# SparkFun_Valve_Control_Shield.net
KiCad netlist of a schematic drawn in EAGLE
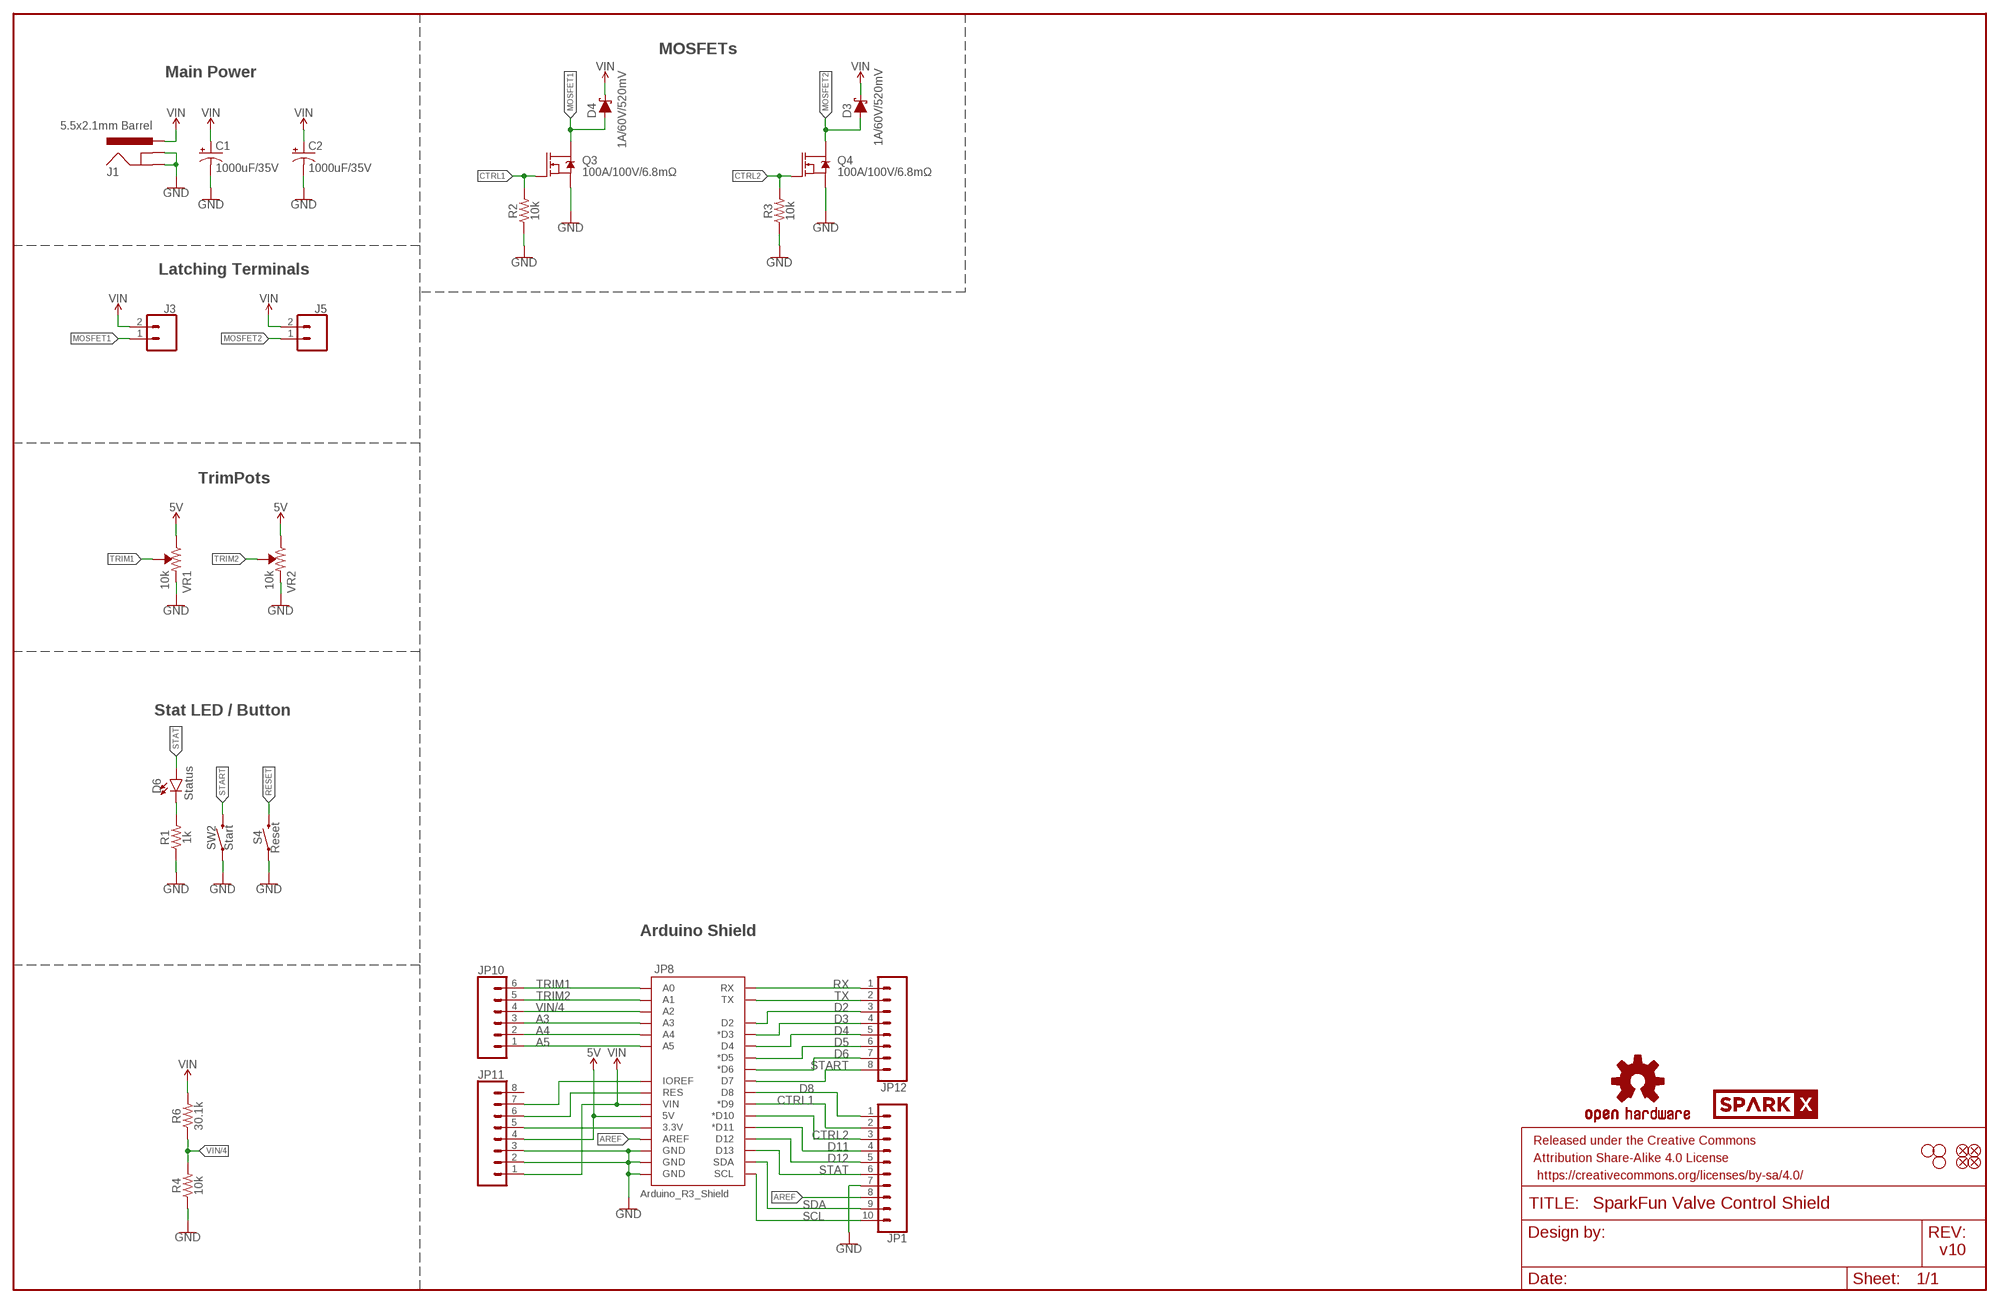
[diagram p0: schematic, sheet 1]

(export (version "E")
  (design (tool "Eeschema 10.0.6"))
  (components
    (comp (ref "C1")
      (value "1000uF/35V")
      (footprint "eagle-import:CPOL-RADIAL-5MM-10MM-KIT")
      (libsource (lib "eagle-import") (part "1000UF-RADIAL-5MM-35V-20%-KIT"))
    )
    (comp (ref "C2")
      (value "1000uF/35V")
      (footprint "eagle-import:CPOL-RADIAL-5MM-10MM-KIT")
      (libsource (lib "eagle-import") (part "1000UF-RADIAL-5MM-35V-20%-KIT"))
    )
    (comp (ref "D3")
      (value "1A/60V/520mV")
      (footprint "eagle-import:DIODE-MICRO-SMP")
      (libsource (lib "eagle-import") (part "DIODE-SCHOTTKY-MSS1P6-M3/89A"))
    )
    (comp (ref "D4")
      (value "1A/60V/520mV")
      (footprint "eagle-import:DIODE-MICRO-SMP")
      (libsource (lib "eagle-import") (part "DIODE-SCHOTTKY-MSS1P6-M3/89A"))
    )
    (comp (ref "D6")
      (value "Status")
      (footprint "eagle-import:LED-1206")
      (libsource (lib "eagle-import") (part "LED1206"))
    )
    (comp (ref "FD1")
      (value "FIDUCIAL1X2")
      (footprint "eagle-import:FIDUCIAL-1X2")
      (libsource (lib "eagle-import") (part "FIDUCIAL1X2"))
    )
    (comp (ref "FD2")
      (value "FIDUCIAL1X2")
      (footprint "eagle-import:FIDUCIAL-1X2")
      (libsource (lib "eagle-import") (part "FIDUCIAL1X2"))
    )
    (comp (ref "FD3")
      (value "FIDUCIAL1X2")
      (footprint "eagle-import:FIDUCIAL-1X2")
      (libsource (lib "eagle-import") (part "FIDUCIAL1X2"))
    )
    (comp (ref "FD4")
      (value "FIDUCIAL1X2")
      (footprint "eagle-import:FIDUCIAL-1X2")
      (libsource (lib "eagle-import") (part "FIDUCIAL1X2"))
    )
    (comp (ref "FRAME2")
      (value "FRAME-LEDGER")
      (footprint "eagle-import:CREATIVE_COMMONS")
      (libsource (lib "eagle-import") (part "FRAME-LEDGER"))
    )
    (comp (ref "H1")
      (value "STAND-OFF")
      (footprint "eagle-import:STAND-OFF")
      (libsource (lib "eagle-import") (part "STAND-OFF"))
    )
    (comp (ref "H2")
      (value "STAND-OFF")
      (footprint "eagle-import:STAND-OFF")
      (libsource (lib "eagle-import") (part "STAND-OFF"))
    )
    (comp (ref "H4")
      (value "STAND-OFF")
      (footprint "eagle-import:STAND-OFF")
      (libsource (lib "eagle-import") (part "STAND-OFF"))
    )
    (comp (ref "J1")
      (value "5.5x2.1mm Barrel")
      (footprint "eagle-import:POWER_JACK_SMD")
      (libsource (lib "eagle-import") (part "POWER_JACKSMD"))
    )
    (comp (ref "J3")
      (value "CONN_02LATCH_2")
      (footprint "eagle-import:LATCHTERMINAL-5MM-2")
      (libsource (lib "eagle-import") (part "CONN_02LATCH_2"))
    )
    (comp (ref "J5")
      (value "CONN_02LATCH_2")
      (footprint "eagle-import:LATCHTERMINAL-5MM-2")
      (libsource (lib "eagle-import") (part "CONN_02LATCH_2"))
    )
    (comp (ref "JP1")
      (value "CONN_10NO_SILK_PTH_FEMALE")
      (footprint "eagle-import:1X10_NO_SILK")
      (libsource (lib "eagle-import") (part "CONN_10NO_SILK_PTH_FEMALE"))
    )
    (comp (ref "JP8")
      (value "ARDUINO_R3_SHIELDNOLABELS")
      (footprint "eagle-import:UNO_R3_SHIELD_NOLABELS")
      (libsource (lib "eagle-import") (part "ARDUINO_R3_SHIELDNOLABELS"))
    )
    (comp (ref "JP10")
      (value "CONN_06NO_SILK_NO_POP")
      (footprint "eagle-import:1X06_NO_SILK")
      (libsource (lib "eagle-import") (part "CONN_06NO_SILK_NO_POP"))
    )
    (comp (ref "JP11")
      (value "CONN_08NO_SILK_FEMALE_PTH")
      (footprint "eagle-import:1X08_NO_SILK")
      (libsource (lib "eagle-import") (part "CONN_08NO_SILK_FEMALE_PTH"))
    )
    (comp (ref "JP12")
      (value "CONN_08NO_SILK_FEMALE_PTH")
      (footprint "eagle-import:1X08_NO_SILK")
      (libsource (lib "eagle-import") (part "CONN_08NO_SILK_FEMALE_PTH"))
    )
    (comp (ref "LOGO1")
      (value "OSHW-LOGOS")
      (footprint "eagle-import:OSHW-LOGO-S")
      (libsource (lib "eagle-import") (part "OSHW-LOGOS"))
    )
    (comp (ref "Q3")
      (value "100A/100V/6.8mΩ")
      (footprint "eagle-import:TO-263_D2PAK")
      (libsource (lib "eagle-import") (part "MOSFET-NCH-PSMN7R0"))
    )
    (comp (ref "Q4")
      (value "100A/100V/6.8mΩ")
      (footprint "eagle-import:TO-263_D2PAK")
      (libsource (lib "eagle-import") (part "MOSFET-NCH-PSMN7R0"))
    )
    (comp (ref "R1")
      (value "1k")
      (footprint "eagle-import:0603")
      (libsource (lib "eagle-import") (part "1KOHM-0603-1/10W-1%"))
    )
    (comp (ref "R2")
      (value "10k")
      (footprint "eagle-import:0603")
      (libsource (lib "eagle-import") (part "10KOHM-0603-1/10W-1%"))
    )
    (comp (ref "R3")
      (value "10k")
      (footprint "eagle-import:0603")
      (libsource (lib "eagle-import") (part "10KOHM-0603-1/10W-1%"))
    )
    (comp (ref "R4")
      (value "10k")
      (footprint "eagle-import:0603")
      (libsource (lib "eagle-import") (part "10KOHM-0603-1/10W-1%"))
    )
    (comp (ref "R6")
      (value "30.1k")
      (footprint "eagle-import:0603")
      (libsource (lib "eagle-import") (part "30.1KOHM-0603-1/10W-1%"))
    )
    (comp (ref "S4")
      (value "Reset")
      (footprint "eagle-import:TACTILE_SWITCH_SMD_5.2MM")
      (libsource (lib "eagle-import") (part "MOMENTARY-SWITCH-SPST-SMD-5.2MM-TALL"))
    )
    (comp (ref "SW2")
      (value "Start")
      (footprint "eagle-import:TACTILE_SWITCH_SMD_5.2MM")
      (libsource (lib "eagle-import") (part "MOMENTARY-SWITCH-SPST-SMD-5.2MM-TALL"))
    )
    (comp (ref "U$1")
      (value "SPARKX-LOGO5")
      (footprint "eagle-import:SPARKX-LARGE")
      (libsource (lib "eagle-import") (part "SPARKX-LOGO5"))
    )
    (comp (ref "VR1")
      (value "10k")
      (footprint "eagle-import:TRIMPOT-PTH-3386U")
      (libsource (lib "eagle-import") (part "TRIMPOT-PTH-10MM-KNOB-1/2W-10%"))
    )
    (comp (ref "VR2")
      (value "10k")
      (footprint "eagle-import:TRIMPOT-PTH-3386U")
      (libsource (lib "eagle-import") (part "TRIMPOT-PTH-10MM-KNOB-1/2W-10%"))
    )
  )
  (nets
    (net (code "1") (name "/A3") (class "Default")
      (node (ref "JP10") (pin "3") (pinfunction "3_3") (pintype "passive"))
      (node (ref "JP8") (pin "A3") (pinfunction "A3_A3") (pintype "bidirectional"))
    )
    (net (code "2") (name "/A4") (class "Default")
      (node (ref "JP10") (pin "2") (pinfunction "2_2") (pintype "passive"))
      (node (ref "JP8") (pin "A4") (pinfunction "A4_A4") (pintype "bidirectional"))
    )
    (net (code "3") (name "/A5") (class "Default")
      (node (ref "JP10") (pin "1") (pinfunction "1_1") (pintype "passive"))
      (node (ref "JP8") (pin "A5") (pinfunction "A5_A5") (pintype "bidirectional"))
    )
    (net (code "4") (name "/D2") (class "Default")
      (node (ref "JP12") (pin "3") (pinfunction "3_3") (pintype "passive"))
      (node (ref "JP8") (pin "D2") (pinfunction "D2_D2") (pintype "bidirectional"))
    )
    (net (code "5") (name "/D3") (class "Default")
      (node (ref "JP12") (pin "4") (pinfunction "4_4") (pintype "passive"))
      (node (ref "JP8") (pin "D3") (pinfunction "*D3_D3") (pintype "bidirectional"))
    )
    (net (code "6") (name "/D4") (class "Default")
      (node (ref "JP12") (pin "5") (pinfunction "5_5") (pintype "passive"))
      (node (ref "JP8") (pin "D4") (pinfunction "D4_D4") (pintype "bidirectional"))
    )
    (net (code "7") (name "/D5") (class "Default")
      (node (ref "JP12") (pin "6") (pinfunction "6_6") (pintype "passive"))
      (node (ref "JP8") (pin "D5") (pinfunction "*D5_D5") (pintype "bidirectional"))
    )
    (net (code "8") (name "/D6") (class "Default")
      (node (ref "JP12") (pin "7") (pinfunction "7_7") (pintype "passive"))
      (node (ref "JP8") (pin "D6") (pinfunction "*D6_D6") (pintype "bidirectional"))
    )
    (net (code "9") (name "/D8") (class "Default")
      (node (ref "JP1") (pin "1") (pinfunction "1_1") (pintype "passive"))
      (node (ref "JP8") (pin "D8") (pinfunction "D8_D8") (pintype "bidirectional"))
    )
    (net (code "10") (name "/D11") (class "Default")
      (node (ref "JP1") (pin "4") (pinfunction "4_4") (pintype "passive"))
      (node (ref "JP8") (pin "D11") (pinfunction "*D11_D11") (pintype "bidirectional"))
    )
    (net (code "11") (name "/D12") (class "Default")
      (node (ref "JP1") (pin "5") (pinfunction "5_5") (pintype "passive"))
      (node (ref "JP8") (pin "D12") (pinfunction "D12_D12") (pintype "bidirectional"))
    )
    (net (code "12") (name "/RX") (class "Default")
      (node (ref "JP12") (pin "1") (pinfunction "1_1") (pintype "passive"))
      (node (ref "JP8") (pin "RX") (pinfunction "RX_RX") (pintype "bidirectional"))
    )
    (net (code "13") (name "/SCL") (class "Default")
      (node (ref "JP1") (pin "10") (pinfunction "10_10") (pintype "passive"))
      (node (ref "JP8") (pin "SCL") (pinfunction "SCL_SCL") (pintype "bidirectional"))
    )
    (net (code "14") (name "/SDA") (class "Default")
      (node (ref "JP1") (pin "9") (pinfunction "9_9") (pintype "passive"))
      (node (ref "JP8") (pin "SDA") (pinfunction "SDA_SDA") (pintype "bidirectional"))
    )
    (net (code "15") (name "/TX") (class "Default")
      (node (ref "JP12") (pin "2") (pinfunction "2_2") (pintype "passive"))
      (node (ref "JP8") (pin "TX") (pinfunction "TX_TX") (pintype "bidirectional"))
    )
    (net (code "16") (name "5V") (class "Default")
      (node (ref "JP11") (pin "4") (pinfunction "4_4") (pintype "passive"))
      (node (ref "JP8") (pin "5V") (pinfunction "5V_5V") (pintype "bidirectional"))
      (node (ref "VR1") (pin "3") (pinfunction "CW_3") (pintype "passive"))
      (node (ref "VR2") (pin "3") (pinfunction "CW_3") (pintype "passive"))
    )
    (net (code "17") (name "AREF") (class "Default")
      (node (ref "JP1") (pin "8") (pinfunction "8_8") (pintype "passive"))
      (node (ref "JP8") (pin "AREF") (pinfunction "AREF_AREF") (pintype "bidirectional"))
    )
    (net (code "18") (name "CTRL1") (class "Default")
      (node (ref "JP1") (pin "2") (pinfunction "2_2") (pintype "passive"))
      (node (ref "JP8") (pin "D9") (pinfunction "*D9_D9") (pintype "bidirectional"))
      (node (ref "Q3") (pin "1") (pinfunction "G_1") (pintype "bidirectional"))
      (node (ref "R2") (pin "2") (pinfunction "2_2") (pintype "passive"))
    )
    (net (code "19") (name "CTRL2") (class "Default")
      (node (ref "JP1") (pin "3") (pinfunction "3_3") (pintype "passive"))
      (node (ref "JP8") (pin "D10") (pinfunction "*D10_D10") (pintype "bidirectional"))
      (node (ref "Q4") (pin "1") (pinfunction "G_1") (pintype "bidirectional"))
      (node (ref "R3") (pin "2") (pinfunction "2_2") (pintype "passive"))
    )
    (net (code "20") (name "GND") (class "Default")
      (node (ref "C1") (pin "-") (pinfunction "-_-") (pintype "passive"))
      (node (ref "C2") (pin "-") (pinfunction "-_-") (pintype "passive"))
      (node (ref "J1") (pin "GND") (pinfunction "GNDBREAK_GND") (pintype "bidirectional"))
      (node (ref "J1") (pin "P$4") (pinfunction "GND_P$4") (pintype "bidirectional"))
      (node (ref "JP1") (pin "7") (pinfunction "7_7") (pintype "passive"))
      (node (ref "JP11") (pin "2") (pinfunction "2_2") (pintype "passive"))
      (node (ref "JP11") (pin "3") (pinfunction "3_3") (pintype "passive"))
      (node (ref "JP8") (pin "GND@0") (pinfunction "GND_GND@0") (pintype "bidirectional"))
      (node (ref "JP8") (pin "GND@1") (pinfunction "GND_GND@1") (pintype "bidirectional"))
      (node (ref "JP8") (pin "GND@2") (pinfunction "GND_GND@2") (pintype "bidirectional"))
      (node (ref "Q3") (pin "3") (pinfunction "S_3") (pintype "bidirectional"))
      (node (ref "Q4") (pin "3") (pinfunction "S_3") (pintype "bidirectional"))
      (node (ref "R1") (pin "1") (pinfunction "1_1") (pintype "passive"))
      (node (ref "R2") (pin "1") (pinfunction "1_1") (pintype "passive"))
      (node (ref "R3") (pin "1") (pinfunction "1_1") (pintype "passive"))
      (node (ref "R4") (pin "1") (pinfunction "1_1") (pintype "passive"))
      (node (ref "S4") (pin "1") (pinfunction "1_1") (pintype "passive"))
      (node (ref "SW2") (pin "1") (pinfunction "1_1") (pintype "passive"))
      (node (ref "VR1") (pin "1") (pinfunction "CCW_1") (pintype "passive"))
      (node (ref "VR2") (pin "1") (pinfunction "CCW_1") (pintype "passive"))
    )
    (net (code "21") (name "MOSFET1") (class "Default")
      (node (ref "D4") (pin "A") (pinfunction "A_A") (pintype "passive"))
      (node (ref "J3") (pin "1") (pinfunction "1_1") (pintype "passive"))
      (node (ref "Q3") (pin "2") (pinfunction "D_2") (pintype "bidirectional"))
    )
    (net (code "22") (name "MOSFET2") (class "Default")
      (node (ref "D3") (pin "A") (pinfunction "A_A") (pintype "passive"))
      (node (ref "J5") (pin "1") (pinfunction "1_1") (pintype "passive"))
      (node (ref "Q4") (pin "2") (pinfunction "D_2") (pintype "bidirectional"))
    )
    (net (code "23") (name "Net-(D6-PadC)") (class "Default")
      (node (ref "D6") (pin "C") (pinfunction "C_C") (pintype "passive"))
      (node (ref "R1") (pin "2") (pinfunction "2_2") (pintype "passive"))
    )
    (net (code "24") (name "Net-(JP11-Pad5)") (class "Default")
      (node (ref "JP11") (pin "5") (pinfunction "5_5") (pintype "passive"))
      (node (ref "JP8") (pin "3.3V") (pinfunction "3.3V_3.3V") (pintype "bidirectional"))
    )
    (net (code "25") (name "Net-(JP11-Pad7)") (class "Default")
      (node (ref "JP11") (pin "7") (pinfunction "7_7") (pintype "passive"))
      (node (ref "JP8") (pin "IOREF") (pinfunction "IOREF_IOREF") (pintype "bidirectional"))
    )
    (net (code "26") (name "RESET") (class "Default")
      (node (ref "JP11") (pin "6") (pinfunction "6_6") (pintype "passive"))
      (node (ref "JP8") (pin "RES") (pinfunction "RES_RES") (pintype "bidirectional"))
      (node (ref "S4") (pin "3") (pinfunction "2_3") (pintype "passive"))
    )
    (net (code "27") (name "START") (class "Default")
      (node (ref "JP12") (pin "8") (pinfunction "8_8") (pintype "passive"))
      (node (ref "JP8") (pin "D7") (pinfunction "D7_D7") (pintype "bidirectional"))
      (node (ref "SW2") (pin "3") (pinfunction "2_3") (pintype "passive"))
    )
    (net (code "28") (name "STAT") (class "Default")
      (node (ref "D6") (pin "A") (pinfunction "A_A") (pintype "passive"))
      (node (ref "JP1") (pin "6") (pinfunction "6_6") (pintype "passive"))
      (node (ref "JP8") (pin "D13") (pinfunction "D13_D13") (pintype "bidirectional"))
    )
    (net (code "29") (name "TRIM1") (class "Default")
      (node (ref "JP10") (pin "6") (pinfunction "6_6") (pintype "passive"))
      (node (ref "JP8") (pin "A0") (pinfunction "A0_A0") (pintype "bidirectional"))
      (node (ref "VR1") (pin "2") (pinfunction "WIPER_2") (pintype "passive"))
    )
    (net (code "30") (name "TRIM2") (class "Default")
      (node (ref "JP10") (pin "5") (pinfunction "5_5") (pintype "passive"))
      (node (ref "JP8") (pin "A1") (pinfunction "A1_A1") (pintype "bidirectional"))
      (node (ref "VR2") (pin "2") (pinfunction "WIPER_2") (pintype "passive"))
    )
    (net (code "31") (name "VIN") (class "Default")
      (node (ref "C1") (pin "+") (pinfunction "+_+") (pintype "passive"))
      (node (ref "C2") (pin "+") (pinfunction "+_+") (pintype "passive"))
      (node (ref "D3") (pin "C") (pinfunction "C_C") (pintype "passive"))
      (node (ref "D4") (pin "C") (pinfunction "C_C") (pintype "passive"))
      (node (ref "J1") (pin "VIN0") (pinfunction "PWR_VIN0") (pintype "bidirectional"))
      (node (ref "J3") (pin "2") (pinfunction "2_2") (pintype "passive"))
      (node (ref "J5") (pin "2") (pinfunction "2_2") (pintype "passive"))
      (node (ref "JP11") (pin "1") (pinfunction "1_1") (pintype "passive"))
      (node (ref "JP8") (pin "VIN") (pinfunction "VIN_VIN") (pintype "bidirectional"))
      (node (ref "R6") (pin "2") (pinfunction "2_2") (pintype "passive"))
    )
    (net (code "32") (name "VIN{slash}4") (class "Default")
      (node (ref "JP10") (pin "4") (pinfunction "4_4") (pintype "passive"))
      (node (ref "JP8") (pin "A2") (pinfunction "A2_A2") (pintype "bidirectional"))
      (node (ref "R4") (pin "2") (pinfunction "2_2") (pintype "passive"))
      (node (ref "R6") (pin "1") (pinfunction "1_1") (pintype "passive"))
    )
    (net (code "33") (name "unconnected-(JP11-Pad8)") (class "Default")
      (node (ref "JP11") (pin "8") (pinfunction "8_8") (pintype "passive"))
    )
  )
)
